# 05-ORStatusLed.net
KiCad netlist of a schematic drawn in Altium Designer
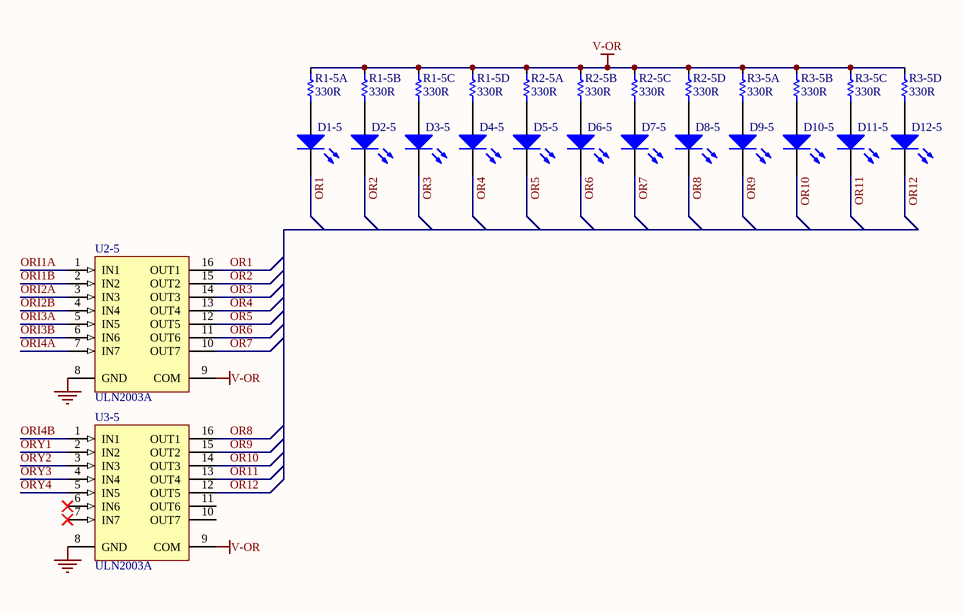
[diagram p0: 05-ORStatusLed.SchDoc]

(export (version "E")
  (design (tool "Eeschema 10.0.6"))
  (components
    (comp (ref "D1-5")
      (value "LED")
      (footprint "LED-0805")
      (description "Typical RED, GREEN, YELLOW, AMBER GaAs LED")
      (fields (field (name "PUBLISHER") "Altium Limited"))
      (libsource (lib "Miscellaneous Devices") (part "LED2"))
    )
    (comp (ref "D2-5")
      (value "LED")
      (footprint "LED-0805")
      (description "Typical RED, GREEN, YELLOW, AMBER GaAs LED")
      (fields (field (name "PUBLISHER") "Altium Limited"))
      (libsource (lib "Miscellaneous Devices") (part "LED2"))
    )
    (comp (ref "D3-5")
      (value "LED")
      (footprint "LED-0805")
      (description "Typical RED, GREEN, YELLOW, AMBER GaAs LED")
      (fields (field (name "PUBLISHER") "Altium Limited"))
      (libsource (lib "Miscellaneous Devices") (part "LED2"))
    )
    (comp (ref "D4-5")
      (value "LED")
      (footprint "LED-0805")
      (description "Typical RED, GREEN, YELLOW, AMBER GaAs LED")
      (fields (field (name "PUBLISHER") "Altium Limited"))
      (libsource (lib "Miscellaneous Devices") (part "LED2"))
    )
    (comp (ref "D5-5")
      (value "LED")
      (footprint "LED-0805")
      (description "Typical RED, GREEN, YELLOW, AMBER GaAs LED")
      (fields (field (name "PUBLISHER") "Altium Limited"))
      (libsource (lib "Miscellaneous Devices") (part "LED2"))
    )
    (comp (ref "D6-5")
      (value "LED")
      (footprint "LED-0805")
      (description "Typical RED, GREEN, YELLOW, AMBER GaAs LED")
      (fields (field (name "PUBLISHER") "Altium Limited"))
      (libsource (lib "Miscellaneous Devices") (part "LED2"))
    )
    (comp (ref "D7-5")
      (value "LED")
      (footprint "LED-0805")
      (description "Typical RED, GREEN, YELLOW, AMBER GaAs LED")
      (fields (field (name "PUBLISHER") "Altium Limited"))
      (libsource (lib "Miscellaneous Devices") (part "LED2"))
    )
    (comp (ref "D8-5")
      (value "LED")
      (footprint "LED-0805")
      (description "Typical RED, GREEN, YELLOW, AMBER GaAs LED")
      (fields (field (name "PUBLISHER") "Altium Limited"))
      (libsource (lib "Miscellaneous Devices") (part "LED2"))
    )
    (comp (ref "D9-5")
      (value "LED")
      (footprint "LED-0805")
      (description "Typical RED, GREEN, YELLOW, AMBER GaAs LED")
      (fields (field (name "PUBLISHER") "Altium Limited"))
      (libsource (lib "Miscellaneous Devices") (part "LED2"))
    )
    (comp (ref "D10-5")
      (value "LED")
      (footprint "LED-0805")
      (description "Typical RED, GREEN, YELLOW, AMBER GaAs LED")
      (fields (field (name "PUBLISHER") "Altium Limited"))
      (libsource (lib "Miscellaneous Devices") (part "LED2"))
    )
    (comp (ref "D11-5")
      (value "LED")
      (footprint "LED-0805")
      (description "Typical RED, GREEN, YELLOW, AMBER GaAs LED")
      (fields (field (name "PUBLISHER") "Altium Limited"))
      (libsource (lib "Miscellaneous Devices") (part "LED2"))
    )
    (comp (ref "D12-5")
      (value "LED")
      (footprint "LED-0805")
      (description "Typical RED, GREEN, YELLOW, AMBER GaAs LED")
      (fields (field (name "PUBLISHER") "Altium Limited"))
      (libsource (lib "Miscellaneous Devices") (part "LED2"))
    )
    (comp (ref "R1-5")
      (value "330R")
      (footprint "R-Array-0603-4")
      (description "RES ARRAY 4 RES 330 OHM 1206")
      (fields
        (field (name "DIGI-KEY PART NUMBER") "Y9331TR-ND")
        (field (name "MANUFACTURER") "Panasonic Electronic Components")
      )
      (libsource (lib "Dlib") (part "Res Array 4"))
    )
    (comp (ref "R2-5")
      (value "330R")
      (footprint "R-Array-0603-4")
      (description "RES ARRAY 4 RES 330 OHM 1206")
      (fields
        (field (name "DIGI-KEY PART NUMBER") "Y9331TR-ND")
        (field (name "MANUFACTURER") "Panasonic Electronic Components")
      )
      (libsource (lib "Dlib") (part "Res Array 4"))
    )
    (comp (ref "R3-5")
      (value "330R")
      (footprint "R-Array-0603-4")
      (description "RES ARRAY 4 RES 330 OHM 1206")
      (fields
        (field (name "DIGI-KEY PART NUMBER") "Y9331TR-ND")
        (field (name "MANUFACTURER") "Panasonic Electronic Components")
      )
      (libsource (lib "Dlib") (part "Res Array 4"))
    )
    (comp (ref "U2-5")
      (value "ULN2003A")
      (footprint "SOIC-16")
      (description "High-Voltage, High-Current Darlington Array")
      (fields (field (name "PUBLISHER") "Altium Limited"))
      (libsource (lib "Allegro Interface Darlington Driver") (part "ULN2003A"))
    )
    (comp (ref "U3-5")
      (value "ULN2003A")
      (footprint "SOIC-16")
      (description "High-Voltage, High-Current Darlington Array")
      (fields (field (name "PUBLISHER") "Altium Limited"))
      (libsource (lib "Allegro Interface Darlington Driver") (part "ULN2003A"))
    )
  )
  (nets
    (net (code "1") (name "/OR1") (class "Default")
      (node (ref "D1-5") (pin "2") (pinfunction "K_2") (pintype "passive"))
      (node (ref "U2-5") (pin "16") (pinfunction "OUT1_16") (pintype "open_collector"))
    )
    (net (code "2") (name "/OR2") (class "Default")
      (node (ref "D2-5") (pin "2") (pinfunction "K_2") (pintype "passive"))
      (node (ref "U2-5") (pin "15") (pinfunction "OUT2_15") (pintype "open_collector"))
    )
    (net (code "3") (name "/OR3") (class "Default")
      (node (ref "D3-5") (pin "2") (pinfunction "K_2") (pintype "passive"))
      (node (ref "U2-5") (pin "14") (pinfunction "OUT3_14") (pintype "open_collector"))
    )
    (net (code "4") (name "/OR4") (class "Default")
      (node (ref "D4-5") (pin "2") (pinfunction "K_2") (pintype "passive"))
      (node (ref "U2-5") (pin "13") (pinfunction "OUT4_13") (pintype "open_collector"))
    )
    (net (code "5") (name "/OR5") (class "Default")
      (node (ref "D5-5") (pin "2") (pinfunction "K_2") (pintype "passive"))
      (node (ref "U2-5") (pin "12") (pinfunction "OUT5_12") (pintype "open_collector"))
    )
    (net (code "6") (name "/OR6") (class "Default")
      (node (ref "D6-5") (pin "2") (pinfunction "K_2") (pintype "passive"))
      (node (ref "U2-5") (pin "11") (pinfunction "OUT6_11") (pintype "open_collector"))
    )
    (net (code "7") (name "/OR7") (class "Default")
      (node (ref "D7-5") (pin "2") (pinfunction "K_2") (pintype "passive"))
      (node (ref "U2-5") (pin "10") (pinfunction "OUT7_10") (pintype "open_collector"))
    )
    (net (code "8") (name "/OR8") (class "Default")
      (node (ref "D8-5") (pin "2") (pinfunction "K_2") (pintype "passive"))
      (node (ref "U3-5") (pin "16") (pinfunction "OUT1_16") (pintype "open_collector"))
    )
    (net (code "9") (name "/OR9") (class "Default")
      (node (ref "D9-5") (pin "2") (pinfunction "K_2") (pintype "passive"))
      (node (ref "U3-5") (pin "15") (pinfunction "OUT2_15") (pintype "open_collector"))
    )
    (net (code "10") (name "/OR10") (class "Default")
      (node (ref "D10-5") (pin "2") (pinfunction "K_2") (pintype "passive"))
      (node (ref "U3-5") (pin "14") (pinfunction "OUT3_14") (pintype "open_collector"))
    )
    (net (code "11") (name "/OR11") (class "Default")
      (node (ref "D11-5") (pin "2") (pinfunction "K_2") (pintype "passive"))
      (node (ref "U3-5") (pin "13") (pinfunction "OUT4_13") (pintype "open_collector"))
    )
    (net (code "12") (name "/OR12") (class "Default")
      (node (ref "D12-5") (pin "2") (pinfunction "K_2") (pintype "passive"))
      (node (ref "U3-5") (pin "12") (pinfunction "OUT5_12") (pintype "open_collector"))
    )
    (net (code "13") (name "/ORI1A") (class "Default")
      (node (ref "U2-5") (pin "1") (pinfunction "IN1_1") (pintype "input"))
    )
    (net (code "14") (name "/ORI1B") (class "Default")
      (node (ref "U2-5") (pin "2") (pinfunction "IN2_2") (pintype "input"))
    )
    (net (code "15") (name "/ORI2A") (class "Default")
      (node (ref "U2-5") (pin "3") (pinfunction "IN3_3") (pintype "input"))
    )
    (net (code "16") (name "/ORI2B") (class "Default")
      (node (ref "U2-5") (pin "4") (pinfunction "IN4_4") (pintype "input"))
    )
    (net (code "17") (name "/ORI3A") (class "Default")
      (node (ref "U2-5") (pin "5") (pinfunction "IN5_5") (pintype "input"))
    )
    (net (code "18") (name "/ORI3B") (class "Default")
      (node (ref "U2-5") (pin "6") (pinfunction "IN6_6") (pintype "input"))
    )
    (net (code "19") (name "/ORI4A") (class "Default")
      (node (ref "U2-5") (pin "7") (pinfunction "IN7_7") (pintype "input"))
    )
    (net (code "20") (name "/ORI4B") (class "Default")
      (node (ref "U3-5") (pin "1") (pinfunction "IN1_1") (pintype "input"))
    )
    (net (code "21") (name "/ORY1") (class "Default")
      (node (ref "U3-5") (pin "2") (pinfunction "IN2_2") (pintype "input"))
    )
    (net (code "22") (name "/ORY2") (class "Default")
      (node (ref "U3-5") (pin "3") (pinfunction "IN3_3") (pintype "input"))
    )
    (net (code "23") (name "/ORY3") (class "Default")
      (node (ref "U3-5") (pin "4") (pinfunction "IN4_4") (pintype "input"))
    )
    (net (code "24") (name "/ORY4") (class "Default")
      (node (ref "U3-5") (pin "5") (pinfunction "IN5_5") (pintype "input"))
    )
    (net (code "25") (name "GND") (class "Default")
      (node (ref "U2-5") (pin "8") (pinfunction "GND_8") (pintype "power_in"))
      (node (ref "U3-5") (pin "8") (pinfunction "GND_8") (pintype "power_in"))
    )
    (net (code "26") (name "Net-(D1-5-A)") (class "Default")
      (node (ref "D1-5") (pin "1") (pinfunction "A_1") (pintype "passive"))
      (node (ref "R1-5") (pin "1") (pinfunction "1_1") (pintype "passive"))
    )
    (net (code "27") (name "Net-(D2-5-A)") (class "Default")
      (node (ref "D2-5") (pin "1") (pinfunction "A_1") (pintype "passive"))
      (node (ref "R1-5") (pin "3") (pinfunction "1_3") (pintype "passive"))
    )
    (net (code "28") (name "Net-(D3-5-A)") (class "Default")
      (node (ref "D3-5") (pin "1") (pinfunction "A_1") (pintype "passive"))
      (node (ref "R1-5") (pin "5") (pinfunction "1_5") (pintype "passive"))
    )
    (net (code "29") (name "Net-(D4-5-A)") (class "Default")
      (node (ref "D4-5") (pin "1") (pinfunction "A_1") (pintype "passive"))
      (node (ref "R1-5") (pin "7") (pinfunction "1_7") (pintype "passive"))
    )
    (net (code "30") (name "Net-(D5-5-A)") (class "Default")
      (node (ref "D5-5") (pin "1") (pinfunction "A_1") (pintype "passive"))
      (node (ref "R2-5") (pin "1") (pinfunction "1_1") (pintype "passive"))
    )
    (net (code "31") (name "Net-(D6-5-A)") (class "Default")
      (node (ref "D6-5") (pin "1") (pinfunction "A_1") (pintype "passive"))
      (node (ref "R2-5") (pin "3") (pinfunction "1_3") (pintype "passive"))
    )
    (net (code "32") (name "Net-(D7-5-A)") (class "Default")
      (node (ref "D7-5") (pin "1") (pinfunction "A_1") (pintype "passive"))
      (node (ref "R2-5") (pin "5") (pinfunction "1_5") (pintype "passive"))
    )
    (net (code "33") (name "Net-(D8-5-A)") (class "Default")
      (node (ref "D8-5") (pin "1") (pinfunction "A_1") (pintype "passive"))
      (node (ref "R2-5") (pin "7") (pinfunction "1_7") (pintype "passive"))
    )
    (net (code "34") (name "Net-(D9-5-A)") (class "Default")
      (node (ref "D9-5") (pin "1") (pinfunction "A_1") (pintype "passive"))
      (node (ref "R3-5") (pin "1") (pinfunction "1_1") (pintype "passive"))
    )
    (net (code "35") (name "Net-(D10-5-A)") (class "Default")
      (node (ref "D10-5") (pin "1") (pinfunction "A_1") (pintype "passive"))
      (node (ref "R3-5") (pin "3") (pinfunction "1_3") (pintype "passive"))
    )
    (net (code "36") (name "Net-(D11-5-A)") (class "Default")
      (node (ref "D11-5") (pin "1") (pinfunction "A_1") (pintype "passive"))
      (node (ref "R3-5") (pin "5") (pinfunction "1_5") (pintype "passive"))
    )
    (net (code "37") (name "Net-(D12-5-A)") (class "Default")
      (node (ref "D12-5") (pin "1") (pinfunction "A_1") (pintype "passive"))
      (node (ref "R3-5") (pin "7") (pinfunction "1_7") (pintype "passive"))
    )
    (net (code "38") (name "V-OR") (class "Default")
      (node (ref "R1-5") (pin "2") (pinfunction "2_2") (pintype "passive"))
      (node (ref "R1-5") (pin "4") (pinfunction "2_4") (pintype "passive"))
      (node (ref "R1-5") (pin "6") (pinfunction "2_6") (pintype "passive"))
      (node (ref "R1-5") (pin "8") (pinfunction "2_8") (pintype "passive"))
      (node (ref "R2-5") (pin "2") (pinfunction "2_2") (pintype "passive"))
      (node (ref "R2-5") (pin "4") (pinfunction "2_4") (pintype "passive"))
      (node (ref "R2-5") (pin "6") (pinfunction "2_6") (pintype "passive"))
      (node (ref "R2-5") (pin "8") (pinfunction "2_8") (pintype "passive"))
      (node (ref "R3-5") (pin "2") (pinfunction "2_2") (pintype "passive"))
      (node (ref "R3-5") (pin "4") (pinfunction "2_4") (pintype "passive"))
      (node (ref "R3-5") (pin "6") (pinfunction "2_6") (pintype "passive"))
      (node (ref "R3-5") (pin "8") (pinfunction "2_8") (pintype "passive"))
      (node (ref "U2-5") (pin "9") (pinfunction "COM_9") (pintype "passive"))
      (node (ref "U3-5") (pin "9") (pinfunction "COM_9") (pintype "passive"))
    )
    (net (code "39") (name "unconnected-(U3-5-IN6-Pad6)") (class "Default")
      (node (ref "U3-5") (pin "6") (pinfunction "IN6_6") (pintype "input+no_connect"))
    )
    (net (code "40") (name "unconnected-(U3-5-IN7-Pad7)") (class "Default")
      (node (ref "U3-5") (pin "7") (pinfunction "IN7_7") (pintype "input+no_connect"))
    )
    (net (code "41") (name "unconnected-(U3-5-OUT6-Pad11)") (class "Default")
      (node (ref "U3-5") (pin "11") (pinfunction "OUT6_11") (pintype "open_collector"))
    )
    (net (code "42") (name "unconnected-(U3-5-OUT7-Pad10)") (class "Default")
      (node (ref "U3-5") (pin "10") (pinfunction "OUT7_10") (pintype "open_collector"))
    )
  )
)
